# uru-card.net
KiCad netlist of a schematic drawn in EAGLE
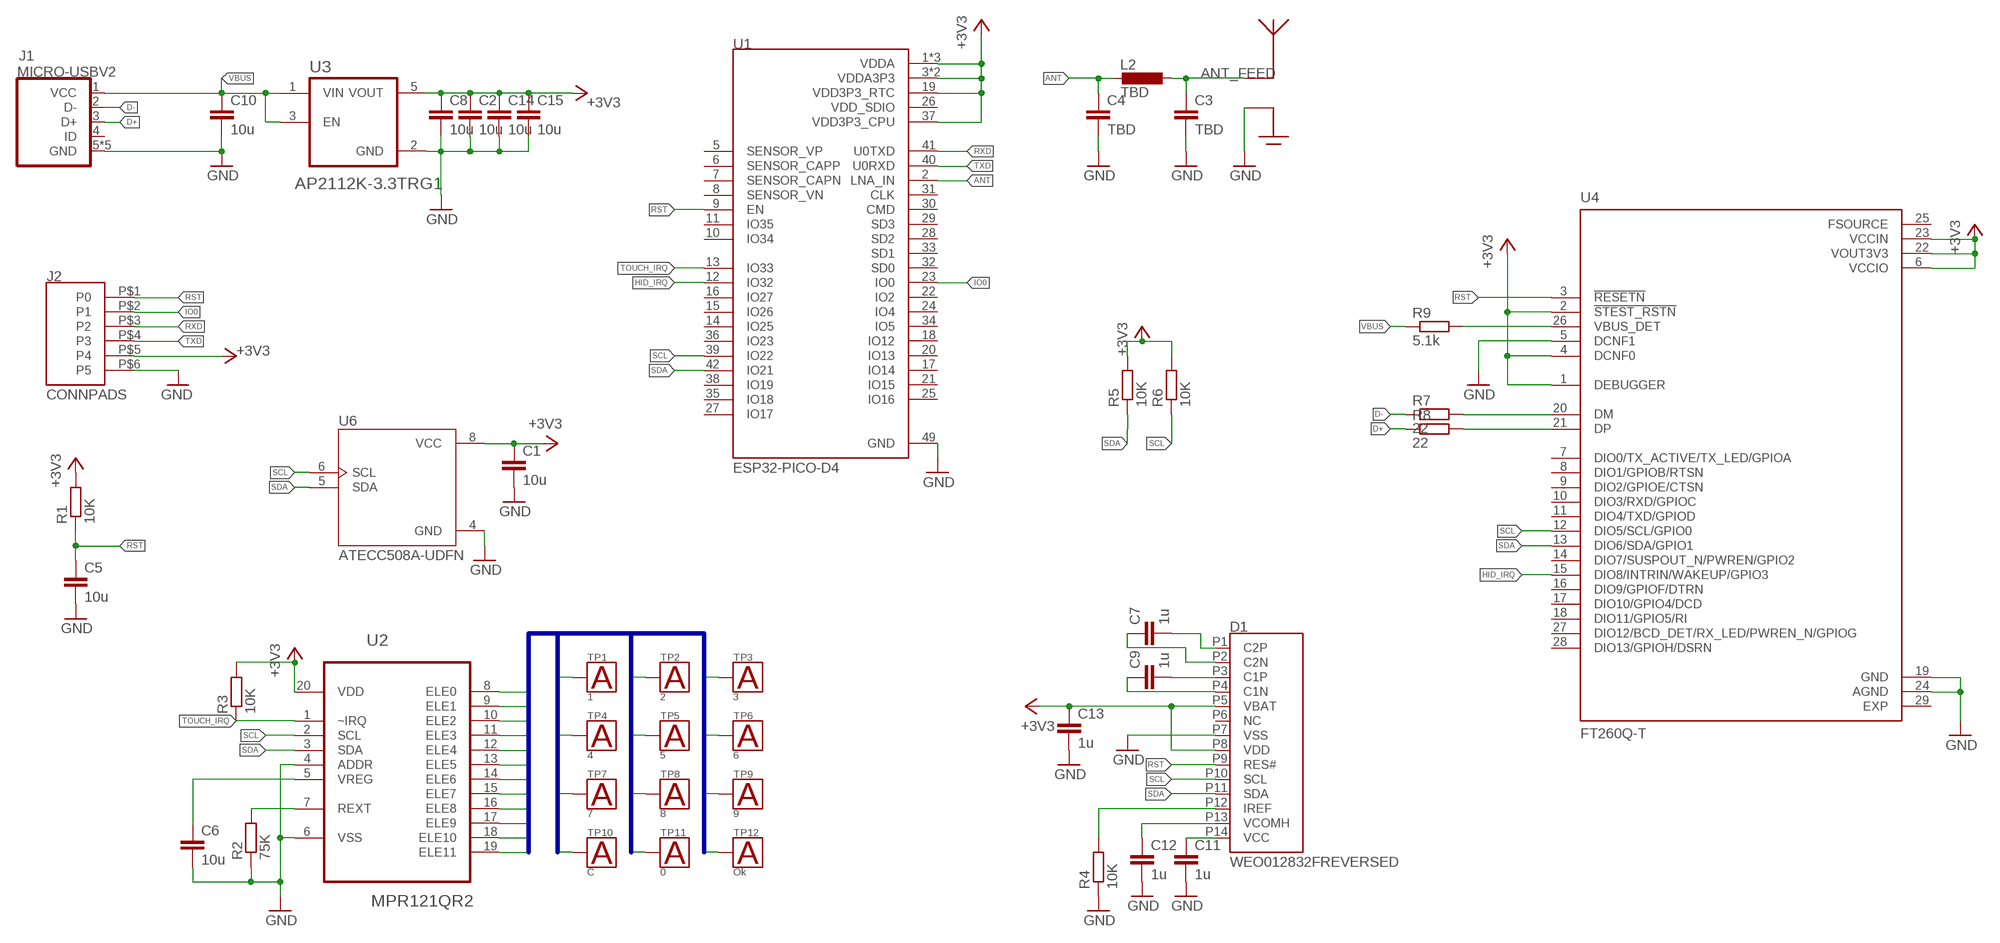
[diagram p0: schematic, sheet 1]

(export (version "E")
  (design (tool "Eeschema 10.0.6"))
  (components
    (comp (ref "C1")
      (value "10u")
      (footprint "eagle-import:C0603")
      (libsource (lib "eagle-import") (part "C-EUC0603"))
    )
    (comp (ref "C2")
      (value "10u")
      (footprint "eagle-import:C0603")
      (libsource (lib "eagle-import") (part "C-EUC0603"))
    )
    (comp (ref "C3")
      (value "TBD")
      (footprint "eagle-import:C0603")
      (libsource (lib "eagle-import") (part "C-EUC0603"))
    )
    (comp (ref "C4")
      (value "TBD")
      (footprint "eagle-import:C0603")
      (libsource (lib "eagle-import") (part "C-EUC0603"))
    )
    (comp (ref "C5")
      (value "10u")
      (footprint "eagle-import:C0603")
      (libsource (lib "eagle-import") (part "C-EUC0603"))
    )
    (comp (ref "C6")
      (value "10u")
      (footprint "eagle-import:C0603")
      (libsource (lib "eagle-import") (part "C-EUC0603"))
    )
    (comp (ref "C7")
      (value "1u")
      (footprint "eagle-import:C0603")
      (libsource (lib "eagle-import") (part "C-EUC0603"))
    )
    (comp (ref "C8")
      (value "10u")
      (footprint "eagle-import:C0603")
      (libsource (lib "eagle-import") (part "C-EUC0603"))
    )
    (comp (ref "C9")
      (value "1u")
      (footprint "eagle-import:C0603")
      (libsource (lib "eagle-import") (part "C-EUC0603"))
    )
    (comp (ref "C10")
      (value "10u")
      (footprint "eagle-import:C0603")
      (libsource (lib "eagle-import") (part "C-EUC0603"))
    )
    (comp (ref "C11")
      (value "1u")
      (footprint "eagle-import:C0603")
      (libsource (lib "eagle-import") (part "C-EUC0603"))
    )
    (comp (ref "C12")
      (value "1u")
      (footprint "eagle-import:C0603")
      (libsource (lib "eagle-import") (part "C-EUC0603"))
    )
    (comp (ref "C13")
      (value "1u")
      (footprint "eagle-import:C0603")
      (libsource (lib "eagle-import") (part "C-EUC0603"))
    )
    (comp (ref "C14")
      (value "10u")
      (footprint "eagle-import:C0603")
      (libsource (lib "eagle-import") (part "C-EUC0603"))
    )
    (comp (ref "C15")
      (value "10u")
      (footprint "eagle-import:C0603")
      (libsource (lib "eagle-import") (part "C-EUC0603"))
    )
    (comp (ref "D1")
      (value "WEO012832FREVERSED")
      (footprint "eagle-import:WEO012832F-REVERSE")
      (libsource (lib "eagle-import") (part "WEO012832FREVERSED"))
    )
    (comp (ref "J1")
      (value "MICRO-USBV2")
      (footprint "eagle-import:MICRO-USB-2")
      (libsource (lib "eagle-import") (part "MICRO-USBV2"))
    )
    (comp (ref "J2")
      (value "CONNPADS")
      (footprint "eagle-import:PADS")
      (libsource (lib "eagle-import") (part "CONNPADS"))
    )
    (comp (ref "L2")
      (value "TBD")
      (footprint "eagle-import:L2012C")
      (libsource (lib "eagle-import") (part "L-EUL2012C"))
    )
    (comp (ref "R1")
      (value "10K")
      (footprint "eagle-import:R0603")
      (libsource (lib "eagle-import") (part "R-EU_R0603"))
    )
    (comp (ref "R2")
      (value "75K")
      (footprint "eagle-import:R0603")
      (libsource (lib "eagle-import") (part "R-EU_R0603"))
    )
    (comp (ref "R3")
      (value "10K")
      (footprint "eagle-import:R0603")
      (libsource (lib "eagle-import") (part "R-EU_R0603"))
    )
    (comp (ref "R4")
      (value "10K")
      (footprint "eagle-import:R0603")
      (libsource (lib "eagle-import") (part "R-EU_R0603"))
    )
    (comp (ref "R5")
      (value "10K")
      (footprint "eagle-import:R0603")
      (libsource (lib "eagle-import") (part "R-EU_R0603"))
    )
    (comp (ref "R6")
      (value "10K")
      (footprint "eagle-import:R0603")
      (libsource (lib "eagle-import") (part "R-EU_R0603"))
    )
    (comp (ref "R7")
      (value "22")
      (footprint "eagle-import:R0603")
      (libsource (lib "eagle-import") (part "R-EU_R0603"))
    )
    (comp (ref "R8")
      (value "22")
      (footprint "eagle-import:R0603")
      (libsource (lib "eagle-import") (part "R-EU_R0603"))
    )
    (comp (ref "R9")
      (value "5.1k")
      (footprint "eagle-import:R0603")
      (libsource (lib "eagle-import") (part "R-EU_R0603"))
    )
    (comp (ref "TP1")
      (value "1")
      (footprint "eagle-import:TOUCH")
      (libsource (lib "eagle-import") (part "TOUCH"))
    )
    (comp (ref "TP2")
      (value "2")
      (footprint "eagle-import:TOUCH")
      (libsource (lib "eagle-import") (part "TOUCH"))
    )
    (comp (ref "TP3")
      (value "3")
      (footprint "eagle-import:TOUCH")
      (libsource (lib "eagle-import") (part "TOUCH"))
    )
    (comp (ref "TP4")
      (value "4")
      (footprint "eagle-import:TOUCH")
      (libsource (lib "eagle-import") (part "TOUCH"))
    )
    (comp (ref "TP5")
      (value "5")
      (footprint "eagle-import:TOUCH")
      (libsource (lib "eagle-import") (part "TOUCH"))
    )
    (comp (ref "TP6")
      (value "6")
      (footprint "eagle-import:TOUCH")
      (libsource (lib "eagle-import") (part "TOUCH"))
    )
    (comp (ref "TP7")
      (value "7")
      (footprint "eagle-import:TOUCH")
      (libsource (lib "eagle-import") (part "TOUCH"))
    )
    (comp (ref "TP8")
      (value "8")
      (footprint "eagle-import:TOUCH")
      (libsource (lib "eagle-import") (part "TOUCH"))
    )
    (comp (ref "TP9")
      (value "9")
      (footprint "eagle-import:TOUCH")
      (libsource (lib "eagle-import") (part "TOUCH"))
    )
    (comp (ref "TP10")
      (value "C")
      (footprint "eagle-import:TOUCH")
      (libsource (lib "eagle-import") (part "TOUCH"))
    )
    (comp (ref "TP11")
      (value "0")
      (footprint "eagle-import:TOUCH")
      (libsource (lib "eagle-import") (part "TOUCH"))
    )
    (comp (ref "TP12")
      (value "Ok")
      (footprint "eagle-import:TOUCH")
      (libsource (lib "eagle-import") (part "TOUCH"))
    )
    (comp (ref "U$15")
      (value "ANT-2_4_PCB")
      (footprint "eagle-import:ANT-2_4")
      (libsource (lib "eagle-import") (part "ANT-2_4_PCB"))
    )
    (comp (ref "U1")
      (value "ESP32-PICO-D4")
      (footprint "eagle-import:PQFN50P700X700X104-49N")
      (fields (field (name "MF") "Espressif Systems"))
      (libsource (lib "eagle-import") (part "ESP32-PICO-D4"))
    )
    (comp (ref "U2")
      (value "MPR121QR2")
      (footprint "eagle-import:QFN40P300X300X60-20N")
      (fields (field (name "MF") "NXP USA"))
      (libsource (lib "eagle-import") (part "MPR121QR2"))
    )
    (comp (ref "U3")
      (value "AP2112K-3.3TRG1")
      (footprint "eagle-import:SOT95P285X140-5N")
      (fields (field (name "MF") "Diodes Inc."))
      (libsource (lib "eagle-import") (part "AP2112K-3.3TRG1"))
    )
    (comp (ref "U4")
      (value "FT260Q-T")
      (footprint "eagle-import:QFN50P500X500X80-29N")
      (fields (field (name "MF") "FTDI,"))
      (libsource (lib "eagle-import") (part "FT260Q-T"))
    )
    (comp (ref "U6")
      (value "ATECC508A-UDFN")
      (footprint "eagle-import:SON50P200X300X60-9N")
      (libsource (lib "eagle-import") (part "ATECC508A-UDFN"))
    )
  )
  (nets
    (net (code "1") (name "+3V3") (class "Default")
      (node (ref "C1") (pin "1") (pinfunction "1_1") (pintype "passive"))
      (node (ref "C13") (pin "1") (pinfunction "1_1") (pintype "passive"))
      (node (ref "C14") (pin "1") (pinfunction "1_1") (pintype "passive"))
      (node (ref "C15") (pin "1") (pinfunction "1_1") (pintype "passive"))
      (node (ref "C2") (pin "1") (pinfunction "1_1") (pintype "passive"))
      (node (ref "C8") (pin "1") (pinfunction "1_1") (pintype "passive"))
      (node (ref "D1") (pin "P5") (pinfunction "VBAT_P5") (pintype "power_in"))
      (node (ref "D1") (pin "P8") (pinfunction "VDD_P8") (pintype "power_in"))
      (node (ref "J2") (pin "P$5") (pinfunction "P4_P$5") (pintype "bidirectional"))
      (node (ref "R1") (pin "2") (pinfunction "2_2") (pintype "passive"))
      (node (ref "R3") (pin "2") (pinfunction "2_2") (pintype "passive"))
      (node (ref "R5") (pin "2") (pinfunction "2_2") (pintype "passive"))
      (node (ref "R6") (pin "2") (pinfunction "2_2") (pintype "passive"))
      (node (ref "U1") (pin "1") (pinfunction "VDDA_1") (pintype "power_in"))
      (node (ref "U1") (pin "19") (pinfunction "VDD3P3_RTC_19") (pintype "power_in"))
      (node (ref "U1") (pin "3") (pinfunction "VDDA3P3_3") (pintype "power_in"))
      (node (ref "U1") (pin "37") (pinfunction "VDD3P3_CPU_37") (pintype "power_in"))
      (node (ref "U1") (pin "4") (pinfunction "VDDA3P3_4") (pintype "power_in"))
      (node (ref "U1") (pin "43") (pinfunction "VDDA_43") (pintype "power_in"))
      (node (ref "U1") (pin "46") (pinfunction "VDDA_46") (pintype "power_in"))
      (node (ref "U2") (pin "20") (pinfunction "VDD_20") (pintype "power_in"))
      (node (ref "U3") (pin "5") (pinfunction "VOUT_5") (pintype "power_in"))
      (node (ref "U4") (pin "1") (pinfunction "DEBUGGER_1") (pintype "bidirectional"))
      (node (ref "U4") (pin "2") (pinfunction "~{STEST_RSTN}_2") (pintype "input"))
      (node (ref "U4") (pin "22") (pinfunction "VOUT3V3_22") (pintype "power_in"))
      (node (ref "U4") (pin "23") (pinfunction "VCCIN_23") (pintype "power_in"))
      (node (ref "U4") (pin "4") (pinfunction "DCNF0_4") (pintype "input"))
      (node (ref "U4") (pin "6") (pinfunction "VCCIO_6") (pintype "power_in"))
      (node (ref "U6") (pin "8") (pinfunction "VCC_8") (pintype "power_in"))
    )
    (net (code "2") (name "/0") (class "Default")
      (node (ref "TP11") (pin "P$1") (pinfunction "P$1_P$1") (pintype "bidirectional"))
      (node (ref "U2") (pin "18") (pinfunction "ELE10_18") (pintype "output"))
    )
    (net (code "3") (name "/1") (class "Default")
      (node (ref "TP1") (pin "P$1") (pinfunction "P$1_P$1") (pintype "bidirectional"))
      (node (ref "U2") (pin "8") (pinfunction "ELE0_8") (pintype "output"))
    )
    (net (code "4") (name "/2") (class "Default")
      (node (ref "TP2") (pin "P$1") (pinfunction "P$1_P$1") (pintype "bidirectional"))
      (node (ref "U2") (pin "9") (pinfunction "ELE1_9") (pintype "output"))
    )
    (net (code "5") (name "/3") (class "Default")
      (node (ref "TP3") (pin "P$1") (pinfunction "P$1_P$1") (pintype "bidirectional"))
      (node (ref "U2") (pin "10") (pinfunction "ELE2_10") (pintype "output"))
    )
    (net (code "6") (name "/4") (class "Default")
      (node (ref "TP4") (pin "P$1") (pinfunction "P$1_P$1") (pintype "bidirectional"))
      (node (ref "U2") (pin "11") (pinfunction "ELE3_11") (pintype "output"))
    )
    (net (code "7") (name "/5") (class "Default")
      (node (ref "TP5") (pin "P$1") (pinfunction "P$1_P$1") (pintype "bidirectional"))
      (node (ref "U2") (pin "12") (pinfunction "ELE4_12") (pintype "output"))
    )
    (net (code "8") (name "/6") (class "Default")
      (node (ref "TP6") (pin "P$1") (pinfunction "P$1_P$1") (pintype "bidirectional"))
      (node (ref "U2") (pin "13") (pinfunction "ELE5_13") (pintype "output"))
    )
    (net (code "9") (name "/7") (class "Default")
      (node (ref "TP7") (pin "P$1") (pinfunction "P$1_P$1") (pintype "bidirectional"))
      (node (ref "U2") (pin "14") (pinfunction "ELE6_14") (pintype "output"))
    )
    (net (code "10") (name "/8") (class "Default")
      (node (ref "TP8") (pin "P$1") (pinfunction "P$1_P$1") (pintype "bidirectional"))
      (node (ref "U2") (pin "15") (pinfunction "ELE7_15") (pintype "output"))
    )
    (net (code "11") (name "/9") (class "Default")
      (node (ref "TP9") (pin "P$1") (pinfunction "P$1_P$1") (pintype "bidirectional"))
      (node (ref "U2") (pin "16") (pinfunction "ELE8_16") (pintype "output"))
    )
    (net (code "12") (name "/ANT_FEED") (class "Default")
      (node (ref "C3") (pin "1") (pinfunction "1_1") (pintype "passive"))
      (node (ref "L2") (pin "1") (pinfunction "1_1") (pintype "passive"))
      (node (ref "U$15") (pin "FEED") (pinfunction "FEED_FEED") (pintype "bidirectional"))
    )
    (net (code "13") (name "/C") (class "Default")
      (node (ref "TP10") (pin "P$1") (pinfunction "P$1_P$1") (pintype "bidirectional"))
      (node (ref "U2") (pin "17") (pinfunction "ELE9_17") (pintype "output"))
    )
    (net (code "14") (name "/EXP") (class "Default")
      (node (ref "U4") (pin "29") (pinfunction "EXP_29") (pintype "power_in"))
    )
    (net (code "15") (name "/FSOURCE") (class "Default")
      (node (ref "U4") (pin "25") (pinfunction "FSOURCE_25") (pintype "power_in"))
    )
    (net (code "16") (name "/OK") (class "Default")
      (node (ref "TP12") (pin "P$1") (pinfunction "P$1_P$1") (pintype "bidirectional"))
      (node (ref "U2") (pin "19") (pinfunction "ELE11_19") (pintype "output"))
    )
    (net (code "17") (name "/VDD_SDIO") (class "Default")
      (node (ref "U1") (pin "26") (pinfunction "VDD_SDIO_26") (pintype "power_in"))
    )
    (net (code "18") (name "ANT") (class "Default")
      (node (ref "C4") (pin "1") (pinfunction "1_1") (pintype "passive"))
      (node (ref "L2") (pin "2") (pinfunction "2_2") (pintype "passive"))
      (node (ref "U1") (pin "2") (pinfunction "LNA_IN_2") (pintype "bidirectional"))
    )
    (net (code "19") (name "D+") (class "Default")
      (node (ref "J1") (pin "3") (pinfunction "D+_3") (pintype "bidirectional"))
      (node (ref "R8") (pin "1") (pinfunction "1_1") (pintype "passive"))
    )
    (net (code "20") (name "D-") (class "Default")
      (node (ref "J1") (pin "2") (pinfunction "D-_2") (pintype "bidirectional"))
      (node (ref "R7") (pin "1") (pinfunction "1_1") (pintype "passive"))
    )
    (net (code "21") (name "GND") (class "Default")
      (node (ref "C1") (pin "2") (pinfunction "2_2") (pintype "passive"))
      (node (ref "C10") (pin "2") (pinfunction "2_2") (pintype "passive"))
      (node (ref "C11") (pin "2") (pinfunction "2_2") (pintype "passive"))
      (node (ref "C12") (pin "2") (pinfunction "2_2") (pintype "passive"))
      (node (ref "C13") (pin "2") (pinfunction "2_2") (pintype "passive"))
      (node (ref "C14") (pin "2") (pinfunction "2_2") (pintype "passive"))
      (node (ref "C15") (pin "2") (pinfunction "2_2") (pintype "passive"))
      (node (ref "C2") (pin "2") (pinfunction "2_2") (pintype "passive"))
      (node (ref "C3") (pin "2") (pinfunction "2_2") (pintype "passive"))
      (node (ref "C4") (pin "2") (pinfunction "2_2") (pintype "passive"))
      (node (ref "C5") (pin "2") (pinfunction "2_2") (pintype "passive"))
      (node (ref "C6") (pin "2") (pinfunction "2_2") (pintype "passive"))
      (node (ref "C8") (pin "2") (pinfunction "2_2") (pintype "passive"))
      (node (ref "D1") (pin "P7") (pinfunction "VSS_P7") (pintype "power_in"))
      (node (ref "J1") (pin "5") (pinfunction "GND_5") (pintype "power_in"))
      (node (ref "J1") (pin "P$1") (pinfunction "GND_P$1") (pintype "power_in"))
      (node (ref "J1") (pin "P$2") (pinfunction "GND_P$2") (pintype "power_in"))
      (node (ref "J1") (pin "P$3") (pinfunction "GND_P$3") (pintype "power_in"))
      (node (ref "J1") (pin "P$4") (pinfunction "GND_P$4") (pintype "power_in"))
      (node (ref "J2") (pin "P$6") (pinfunction "P5_P$6") (pintype "bidirectional"))
      (node (ref "R2") (pin "1") (pinfunction "1_1") (pintype "passive"))
      (node (ref "R4") (pin "1") (pinfunction "1_1") (pintype "passive"))
      (node (ref "U$15") (pin "GND") (pinfunction "GND_GND") (pintype "power_in"))
      (node (ref "U1") (pin "49") (pinfunction "GND_49") (pintype "power_in"))
      (node (ref "U2") (pin "4") (pinfunction "ADDR_4") (pintype "input"))
      (node (ref "U2") (pin "6") (pinfunction "VSS_6") (pintype "power_in"))
      (node (ref "U3") (pin "2") (pinfunction "GND_2") (pintype "power_in"))
      (node (ref "U4") (pin "19") (pinfunction "GND_19") (pintype "power_in"))
      (node (ref "U4") (pin "24") (pinfunction "AGND_24") (pintype "power_in"))
      (node (ref "U4") (pin "5") (pinfunction "DCNF1_5") (pintype "input"))
      (node (ref "U6") (pin "4") (pinfunction "GND_4") (pintype "power_in"))
    )
    (net (code "22") (name "HID_IRQ") (class "Default")
      (node (ref "U1") (pin "12") (pinfunction "IO32_12") (pintype "bidirectional"))
      (node (ref "U4") (pin "15") (pinfunction "DIO8/INTRIN/WAKEUP/GPIO3_15") (pintype "bidirectional"))
    )
    (net (code "23") (name "IO0") (class "Default")
      (node (ref "J2") (pin "P$2") (pinfunction "P1_P$2") (pintype "bidirectional"))
      (node (ref "U1") (pin "23") (pinfunction "IO0_23") (pintype "bidirectional"))
    )
    (net (code "24") (name "Net-(D1-C1N)") (class "Default")
      (node (ref "C9") (pin "1") (pinfunction "1_1") (pintype "passive"))
      (node (ref "D1") (pin "P4") (pinfunction "C1N_P4") (pintype "bidirectional"))
    )
    (net (code "25") (name "Net-(D1-C1P)") (class "Default")
      (node (ref "C9") (pin "2") (pinfunction "2_2") (pintype "passive"))
      (node (ref "D1") (pin "P3") (pinfunction "C1P_P3") (pintype "bidirectional"))
    )
    (net (code "26") (name "Net-(D1-C2N)") (class "Default")
      (node (ref "C7") (pin "1") (pinfunction "1_1") (pintype "passive"))
      (node (ref "D1") (pin "P2") (pinfunction "C2N_P2") (pintype "bidirectional"))
    )
    (net (code "27") (name "Net-(D1-C2P)") (class "Default")
      (node (ref "C7") (pin "2") (pinfunction "2_2") (pintype "passive"))
      (node (ref "D1") (pin "P1") (pinfunction "C2P_P1") (pintype "bidirectional"))
    )
    (net (code "28") (name "Net-(D1-IREF)") (class "Default")
      (node (ref "D1") (pin "P12") (pinfunction "IREF_P12") (pintype "bidirectional"))
      (node (ref "R4") (pin "2") (pinfunction "2_2") (pintype "passive"))
    )
    (net (code "29") (name "Net-(D1-VCC)") (class "Default")
      (node (ref "C11") (pin "1") (pinfunction "1_1") (pintype "passive"))
      (node (ref "D1") (pin "P14") (pinfunction "VCC_P14") (pintype "power_in"))
    )
    (net (code "30") (name "Net-(D1-VCOMH)") (class "Default")
      (node (ref "C12") (pin "1") (pinfunction "1_1") (pintype "passive"))
      (node (ref "D1") (pin "P13") (pinfunction "VCOMH_P13") (pintype "input"))
    )
    (net (code "31") (name "Net-(U2-REXT)") (class "Default")
      (node (ref "R2") (pin "2") (pinfunction "2_2") (pintype "passive"))
      (node (ref "U2") (pin "7") (pinfunction "REXT_7") (pintype "input"))
    )
    (net (code "32") (name "Net-(U2-VREG)") (class "Default")
      (node (ref "C6") (pin "1") (pinfunction "1_1") (pintype "passive"))
      (node (ref "U2") (pin "5") (pinfunction "VREG_5") (pintype "input"))
    )
    (net (code "33") (name "Net-(U4-DM)") (class "Default")
      (node (ref "R7") (pin "2") (pinfunction "2_2") (pintype "passive"))
      (node (ref "U4") (pin "20") (pinfunction "DM_20") (pintype "bidirectional"))
    )
    (net (code "34") (name "Net-(U4-DP)") (class "Default")
      (node (ref "R8") (pin "2") (pinfunction "2_2") (pintype "passive"))
      (node (ref "U4") (pin "21") (pinfunction "DP_21") (pintype "bidirectional"))
    )
    (net (code "35") (name "Net-(U4-VBUS_DET)") (class "Default")
      (node (ref "R9") (pin "2") (pinfunction "2_2") (pintype "passive"))
      (node (ref "U4") (pin "26") (pinfunction "VBUS_DET_26") (pintype "input"))
    )
    (net (code "36") (name "RST") (class "Default")
      (node (ref "C5") (pin "1") (pinfunction "1_1") (pintype "passive"))
      (node (ref "D1") (pin "P9") (pinfunction "RES#_P9") (pintype "input"))
      (node (ref "J2") (pin "P$1") (pinfunction "P0_P$1") (pintype "bidirectional"))
      (node (ref "R1") (pin "1") (pinfunction "1_1") (pintype "passive"))
      (node (ref "U1") (pin "9") (pinfunction "EN_9") (pintype "input"))
      (node (ref "U4") (pin "3") (pinfunction "~{RESETN}_3") (pintype "input"))
    )
    (net (code "37") (name "RXD") (class "Default")
      (node (ref "J2") (pin "P$3") (pinfunction "P2_P$3") (pintype "bidirectional"))
      (node (ref "U1") (pin "41") (pinfunction "U0TXD_41") (pintype "bidirectional"))
    )
    (net (code "38") (name "SCL") (class "Default")
      (node (ref "D1") (pin "P10") (pinfunction "SCL_P10") (pintype "bidirectional"))
      (node (ref "R6") (pin "1") (pinfunction "1_1") (pintype "passive"))
      (node (ref "U1") (pin "39") (pinfunction "IO22_39") (pintype "bidirectional"))
      (node (ref "U2") (pin "2") (pinfunction "SCL_2") (pintype "input"))
      (node (ref "U4") (pin "12") (pinfunction "DIO5/SCL/GPIO0_12") (pintype "bidirectional"))
      (node (ref "U6") (pin "6") (pinfunction "SCL_6") (pintype "input"))
    )
    (net (code "39") (name "SDA") (class "Default")
      (node (ref "D1") (pin "P11") (pinfunction "SDA_P11") (pintype "bidirectional"))
      (node (ref "R5") (pin "1") (pinfunction "1_1") (pintype "passive"))
      (node (ref "U1") (pin "42") (pinfunction "IO21_42") (pintype "bidirectional"))
      (node (ref "U2") (pin "3") (pinfunction "SDA_3") (pintype "input"))
      (node (ref "U4") (pin "13") (pinfunction "DIO6/SDA/GPIO1_13") (pintype "bidirectional"))
      (node (ref "U6") (pin "5") (pinfunction "SDA_5") (pintype "bidirectional"))
    )
    (net (code "40") (name "TOUCH_IRQ") (class "Default")
      (node (ref "R3") (pin "1") (pinfunction "1_1") (pintype "passive"))
      (node (ref "U1") (pin "13") (pinfunction "IO33_13") (pintype "bidirectional"))
      (node (ref "U2") (pin "1") (pinfunction "~{IRQ}_1") (pintype "input"))
    )
    (net (code "41") (name "TXD") (class "Default")
      (node (ref "J2") (pin "P$4") (pinfunction "P3_P$4") (pintype "bidirectional"))
      (node (ref "U1") (pin "40") (pinfunction "U0RXD_40") (pintype "bidirectional"))
    )
    (net (code "42") (name "VBUS") (class "Default")
      (node (ref "C10") (pin "1") (pinfunction "1_1") (pintype "passive"))
      (node (ref "J1") (pin "1") (pinfunction "VCC_1") (pintype "power_in"))
      (node (ref "R9") (pin "1") (pinfunction "1_1") (pintype "passive"))
      (node (ref "U3") (pin "1") (pinfunction "VIN_1") (pintype "power_in"))
      (node (ref "U3") (pin "3") (pinfunction "EN_3") (pintype "input"))
    )
    (net (code "43") (name "unconnected-(D1-NC-PadP6)") (class "Default")
      (node (ref "D1") (pin "P6") (pinfunction "NC_P6") (pintype "no_connect"))
    )
    (net (code "44") (name "unconnected-(J1-ID-Pad4)") (class "Default")
      (node (ref "J1") (pin "4") (pinfunction "ID_4") (pintype "bidirectional"))
    )
    (net (code "45") (name "unconnected-(U1-CLK-Pad31)") (class "Default")
      (node (ref "U1") (pin "31") (pinfunction "CLK_31") (pintype "bidirectional"))
    )
    (net (code "46") (name "unconnected-(U1-CMD-Pad30)") (class "Default")
      (node (ref "U1") (pin "30") (pinfunction "CMD_30") (pintype "bidirectional"))
    )
    (net (code "47") (name "unconnected-(U1-IO2-Pad22)") (class "Default")
      (node (ref "U1") (pin "22") (pinfunction "IO2_22") (pintype "bidirectional"))
    )
    (net (code "48") (name "unconnected-(U1-IO4-Pad24)") (class "Default")
      (node (ref "U1") (pin "24") (pinfunction "IO4_24") (pintype "bidirectional"))
    )
    (net (code "49") (name "unconnected-(U1-IO5-Pad34)") (class "Default")
      (node (ref "U1") (pin "34") (pinfunction "IO5_34") (pintype "bidirectional"))
    )
    (net (code "50") (name "unconnected-(U1-IO12-Pad18)") (class "Default")
      (node (ref "U1") (pin "18") (pinfunction "IO12_18") (pintype "bidirectional"))
    )
    (net (code "51") (name "unconnected-(U1-IO13-Pad20)") (class "Default")
      (node (ref "U1") (pin "20") (pinfunction "IO13_20") (pintype "bidirectional"))
    )
    (net (code "52") (name "unconnected-(U1-IO14-Pad17)") (class "Default")
      (node (ref "U1") (pin "17") (pinfunction "IO14_17") (pintype "bidirectional"))
    )
    (net (code "53") (name "unconnected-(U1-IO15-Pad21)") (class "Default")
      (node (ref "U1") (pin "21") (pinfunction "IO15_21") (pintype "bidirectional"))
    )
    (net (code "54") (name "unconnected-(U1-IO16-Pad25)") (class "Default")
      (node (ref "U1") (pin "25") (pinfunction "IO16_25") (pintype "bidirectional"))
    )
    (net (code "55") (name "unconnected-(U1-IO17-Pad27)") (class "Default")
      (node (ref "U1") (pin "27") (pinfunction "IO17_27") (pintype "bidirectional"))
    )
    (net (code "56") (name "unconnected-(U1-IO18-Pad35)") (class "Default")
      (node (ref "U1") (pin "35") (pinfunction "IO18_35") (pintype "bidirectional"))
    )
    (net (code "57") (name "unconnected-(U1-IO19-Pad38)") (class "Default")
      (node (ref "U1") (pin "38") (pinfunction "IO19_38") (pintype "bidirectional"))
    )
    (net (code "58") (name "unconnected-(U1-IO23-Pad36)") (class "Default")
      (node (ref "U1") (pin "36") (pinfunction "IO23_36") (pintype "bidirectional"))
    )
    (net (code "59") (name "unconnected-(U1-IO25-Pad14)") (class "Default")
      (node (ref "U1") (pin "14") (pinfunction "IO25_14") (pintype "bidirectional"))
    )
    (net (code "60") (name "unconnected-(U1-IO26-Pad15)") (class "Default")
      (node (ref "U1") (pin "15") (pinfunction "IO26_15") (pintype "bidirectional"))
    )
    (net (code "61") (name "unconnected-(U1-IO27-Pad16)") (class "Default")
      (node (ref "U1") (pin "16") (pinfunction "IO27_16") (pintype "bidirectional"))
    )
    (net (code "62") (name "unconnected-(U1-IO34-Pad10)") (class "Default")
      (node (ref "U1") (pin "10") (pinfunction "IO34_10") (pintype "input"))
    )
    (net (code "63") (name "unconnected-(U1-IO35-Pad11)") (class "Default")
      (node (ref "U1") (pin "11") (pinfunction "IO35_11") (pintype "input"))
    )
    (net (code "64") (name "unconnected-(U1-SD0-Pad32)") (class "Default")
      (node (ref "U1") (pin "32") (pinfunction "SD0_32") (pintype "bidirectional"))
    )
    (net (code "65") (name "unconnected-(U1-SD1-Pad33)") (class "Default")
      (node (ref "U1") (pin "33") (pinfunction "SD1_33") (pintype "bidirectional"))
    )
    (net (code "66") (name "unconnected-(U1-SD2-Pad28)") (class "Default")
      (node (ref "U1") (pin "28") (pinfunction "SD2_28") (pintype "bidirectional"))
    )
    (net (code "67") (name "unconnected-(U1-SD3-Pad29)") (class "Default")
      (node (ref "U1") (pin "29") (pinfunction "SD3_29") (pintype "bidirectional"))
    )
    (net (code "68") (name "unconnected-(U1-SENSOR_CAPN-Pad7)") (class "Default")
      (node (ref "U1") (pin "7") (pinfunction "SENSOR_CAPN_7") (pintype "input"))
    )
    (net (code "69") (name "unconnected-(U1-SENSOR_CAPP-Pad6)") (class "Default")
      (node (ref "U1") (pin "6") (pinfunction "SENSOR_CAPP_6") (pintype "input"))
    )
    (net (code "70") (name "unconnected-(U1-SENSOR_VN-Pad8)") (class "Default")
      (node (ref "U1") (pin "8") (pinfunction "SENSOR_VN_8") (pintype "input"))
    )
    (net (code "71") (name "unconnected-(U1-SENSOR_VP-Pad5)") (class "Default")
      (node (ref "U1") (pin "5") (pinfunction "SENSOR_VP_5") (pintype "input"))
    )
    (net (code "72") (name "unconnected-(U4-DIO0{slash}TX_ACTIVE{slash}TX_LED{slash}GPIOA-Pad7)") (class "Default")
      (node (ref "U4") (pin "7") (pinfunction "DIO0/TX_ACTIVE/TX_LED/GPIOA_7") (pintype "bidirectional"))
    )
    (net (code "73") (name "unconnected-(U4-DIO1{slash}GPIOB{slash}RTSN-Pad8)") (class "Default")
      (node (ref "U4") (pin "8") (pinfunction "DIO1/GPIOB/RTSN_8") (pintype "bidirectional"))
    )
    (net (code "74") (name "unconnected-(U4-DIO2{slash}GPIOE{slash}CTSN-Pad9)") (class "Default")
      (node (ref "U4") (pin "9") (pinfunction "DIO2/GPIOE/CTSN_9") (pintype "bidirectional"))
    )
    (net (code "75") (name "unconnected-(U4-DIO3{slash}RXD{slash}GPIOC-Pad10)") (class "Default")
      (node (ref "U4") (pin "10") (pinfunction "DIO3/RXD/GPIOC_10") (pintype "bidirectional"))
    )
    (net (code "76") (name "unconnected-(U4-DIO4{slash}TXD{slash}GPIOD-Pad11)") (class "Default")
      (node (ref "U4") (pin "11") (pinfunction "DIO4/TXD/GPIOD_11") (pintype "bidirectional"))
    )
    (net (code "77") (name "unconnected-(U4-DIO7{slash}SUSPOUT_N{slash}PWREN{slash}GPIO2-Pad14)") (class "Default")
      (node (ref "U4") (pin "14") (pinfunction "DIO7/SUSPOUT_N/PWREN/GPIO2_14") (pintype "bidirectional"))
    )
    (net (code "78") (name "unconnected-(U4-DIO9{slash}GPIOF{slash}DTRN-Pad16)") (class "Default")
      (node (ref "U4") (pin "16") (pinfunction "DIO9/GPIOF/DTRN_16") (pintype "bidirectional"))
    )
    (net (code "79") (name "unconnected-(U4-DIO10{slash}GPIO4{slash}DCD-Pad17)") (class "Default")
      (node (ref "U4") (pin "17") (pinfunction "DIO10/GPIO4/DCD_17") (pintype "bidirectional"))
    )
    (net (code "80") (name "unconnected-(U4-DIO11{slash}GPIO5{slash}RI-Pad18)") (class "Default")
      (node (ref "U4") (pin "18") (pinfunction "DIO11/GPIO5/RI_18") (pintype "bidirectional"))
    )
    (net (code "81") (name "unconnected-(U4-DIO12{slash}BCD_DET{slash}RX_LED{slash}PWREN_N{slash}GPIOG-Pad27)") (class "Default")
      (node (ref "U4") (pin "27") (pinfunction "DIO12/BCD_DET/RX_LED/PWREN_N/GPIOG_27") (pintype "bidirectional"))
    )
    (net (code "82") (name "unconnected-(U4-DIO13{slash}GPIOH{slash}DSRN-Pad28)") (class "Default")
      (node (ref "U4") (pin "28") (pinfunction "DIO13/GPIOH/DSRN_28") (pintype "bidirectional"))
    )
  )
)
